# ME433_schematic.net
KiCad netlist of a schematic drawn in EAGLE
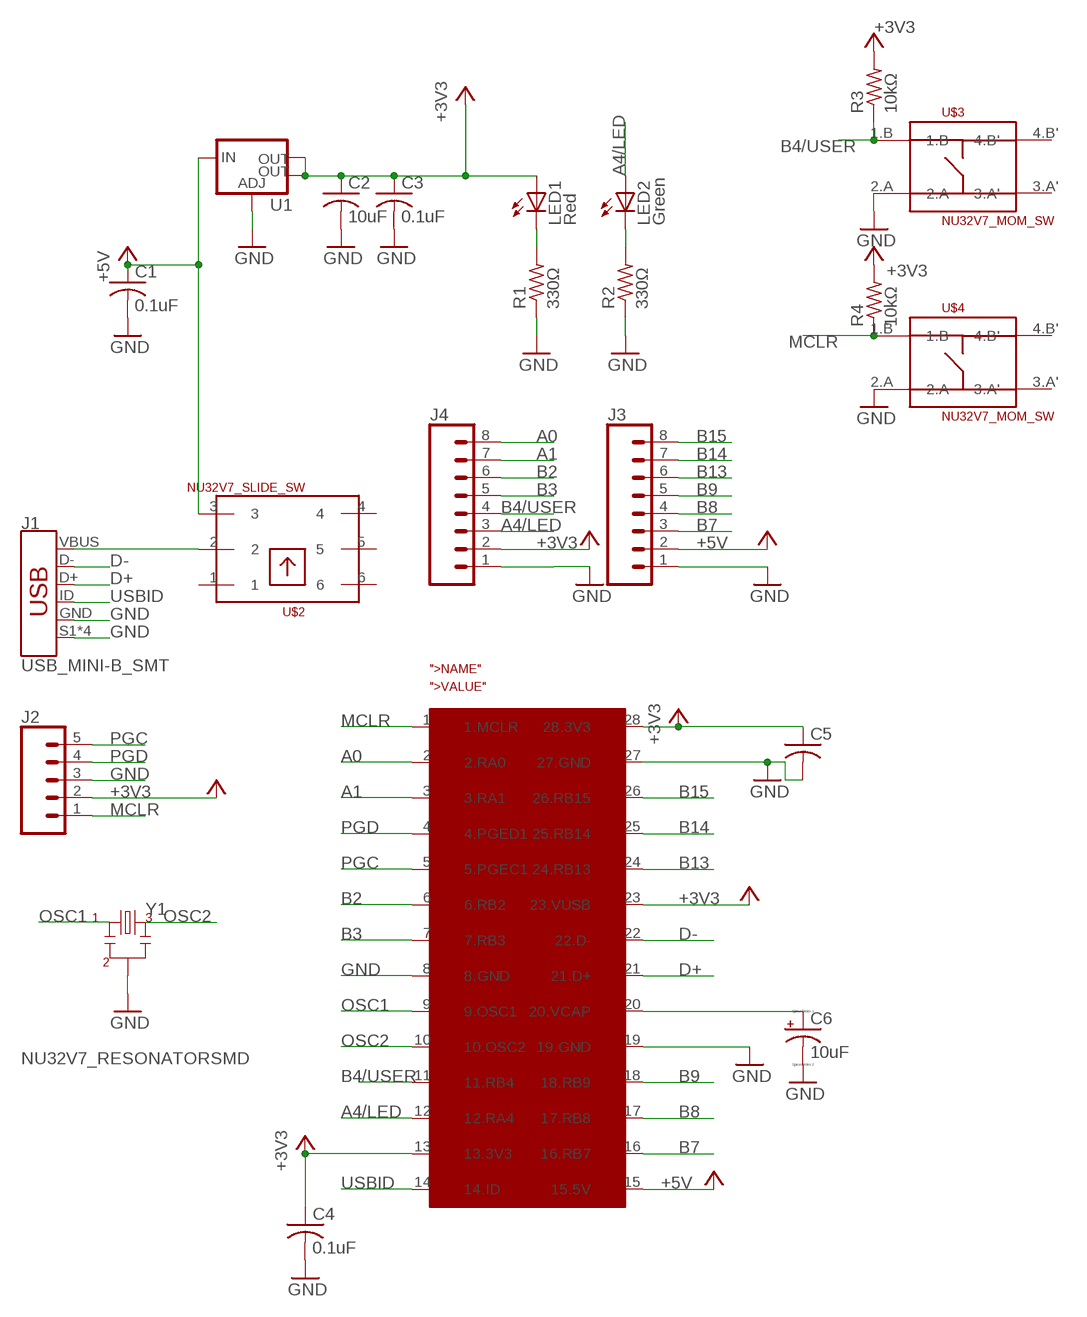
[diagram p0: schematic, sheet 1]

(export (version "E")
  (design (tool "Eeschema 10.0.6"))
  (components
    (comp (ref "C1")
      (value "0.1uF")
      (footprint "eagle-import:C0603")
      (libsource (lib "eagle-import") (part "C-USC0603"))
    )
    (comp (ref "C2")
      (value "10uF")
      (footprint "eagle-import:C0603")
      (libsource (lib "eagle-import") (part "C-USC0603"))
    )
    (comp (ref "C3")
      (value "0.1uF")
      (footprint "eagle-import:C0603")
      (libsource (lib "eagle-import") (part "C-USC0603"))
    )
    (comp (ref "C4")
      (value "0.1uF")
      (footprint "eagle-import:C0603")
      (libsource (lib "eagle-import") (part "C-USC0603"))
    )
    (comp (ref "C5")
      (value "C-USC0603")
      (footprint "eagle-import:C0603")
      (libsource (lib "eagle-import") (part "C-USC0603"))
    )
    (comp (ref "C6")
      (value "10uF")
      (footprint "eagle-import:153CLV-0605")
      (libsource (lib "eagle-import") (part "CPOL-US153CLV-0605"))
    )
    (comp (ref "J1")
      (value "USB_MINI-B_SMT")
      (footprint "eagle-import:USB-MINIB")
      (libsource (lib "eagle-import") (part "USB_MINI-B_SMT"))
    )
    (comp (ref "J2")
      (value "CONN_05")
      (footprint "eagle-import:1X05")
      (libsource (lib "eagle-import") (part "CONN_05"))
    )
    (comp (ref "J3")
      (value "CONN_08\"")
      (footprint "eagle-import:1X08")
      (libsource (lib "eagle-import") (part "CONN_08{dblquote}"))
    )
    (comp (ref "J4")
      (value "CONN_08\"")
      (footprint "eagle-import:1X08")
      (libsource (lib "eagle-import") (part "CONN_08{dblquote}"))
    )
    (comp (ref "LED1")
      (value "Red")
      (footprint "eagle-import:SML0603")
      (libsource (lib "eagle-import") (part "LEDSML0603"))
    )
    (comp (ref "LED2")
      (value "Green")
      (footprint "eagle-import:SML0603")
      (libsource (lib "eagle-import") (part "LEDSML0603"))
    )
    (comp (ref "R1")
      (value "330Ω")
      (footprint "eagle-import:R0603")
      (libsource (lib "eagle-import") (part "R-US_R0603"))
    )
    (comp (ref "R2")
      (value "330Ω")
      (footprint "eagle-import:R0603")
      (libsource (lib "eagle-import") (part "R-US_R0603"))
    )
    (comp (ref "R3")
      (value "10kΩ")
      (footprint "eagle-import:R0603")
      (libsource (lib "eagle-import") (part "R-US_R0603"))
    )
    (comp (ref "R4")
      (value "10kΩ")
      (footprint "eagle-import:R0603")
      (libsource (lib "eagle-import") (part "R-US_R0603"))
    )
    (comp (ref "U$1")
      (value "PIC32")
      (footprint "eagle-import:DIL28-3")
      (libsource (lib "eagle-import") (part "PIC32"))
    )
    (comp (ref "U$2")
      (value "NU32V7_SLIDE_SW")
      (footprint "eagle-import:NU32V7_SLIDE_SW")
      (libsource (lib "eagle-import") (part "NU32V7_SLIDE_SW"))
    )
    (comp (ref "U$3")
      (value "NU32V7_MOM_SW")
      (footprint "eagle-import:NU32V7_MOM_SW")
      (libsource (lib "eagle-import") (part "NU32V7_MOM_SW"))
    )
    (comp (ref "U$4")
      (value "NU32V7_MOM_SW")
      (footprint "eagle-import:NU32V7_MOM_SW")
      (libsource (lib "eagle-import") (part "NU32V7_MOM_SW"))
    )
    (comp (ref "U1")
      (value "NU32V7_V_REG_LM1117SOT223")
      (footprint "eagle-import:NU32V7_SOT223")
      (libsource (lib "eagle-import") (part "NU32V7_V_REG_LM1117SOT223"))
    )
    (comp (ref "Y1")
      (value "NU32V7_RESONATORSMD")
      (footprint "eagle-import:NU32V7_RESONATOR-SMD")
      (libsource (lib "eagle-import") (part "NU32V7_RESONATORSMD"))
    )
  )
  (nets
    (net (code "1") (name "+3V3") (class "Default")
      (node (ref "C2") (pin "1") (pinfunction "1_1") (pintype "passive"))
      (node (ref "C3") (pin "1") (pinfunction "1_1") (pintype "passive"))
      (node (ref "C4") (pin "1") (pinfunction "1_1") (pintype "passive"))
      (node (ref "C5") (pin "1") (pinfunction "1_1") (pintype "passive"))
      (node (ref "J2") (pin "2") (pinfunction "2_2") (pintype "passive"))
      (node (ref "J4") (pin "2") (pinfunction "2_2") (pintype "passive"))
      (node (ref "LED1") (pin "A") (pinfunction "A_A") (pintype "passive"))
      (node (ref "R3") (pin "2") (pinfunction "2_2") (pintype "passive"))
      (node (ref "R4") (pin "2") (pinfunction "2_2") (pintype "passive"))
      (node (ref "U$1") (pin "13") (pinfunction "13.3V3_13") (pintype "bidirectional"))
      (node (ref "U$1") (pin "23") (pinfunction "23.VUSB_23") (pintype "bidirectional"))
      (node (ref "U$1") (pin "28") (pinfunction "28.3V3_28") (pintype "bidirectional"))
      (node (ref "U1") (pin "2") (pinfunction "OUT_2") (pintype "output"))
      (node (ref "U1") (pin "4") (pinfunction "OUT_4") (pintype "output"))
    )
    (net (code "2") (name "+5V") (class "Default")
      (node (ref "C1") (pin "1") (pinfunction "1_1") (pintype "passive"))
      (node (ref "J3") (pin "2") (pinfunction "2_2") (pintype "passive"))
      (node (ref "U$1") (pin "15") (pinfunction "15.5V_15") (pintype "bidirectional"))
      (node (ref "U$2") (pin "3") (pinfunction "3_3") (pintype "bidirectional"))
      (node (ref "U1") (pin "3") (pinfunction "IN_3") (pintype "input"))
    )
    (net (code "3") (name "/A0") (class "Default")
      (node (ref "J4") (pin "8") (pinfunction "8_8") (pintype "passive"))
      (node (ref "U$1") (pin "2") (pinfunction "2.RA0_2") (pintype "bidirectional"))
    )
    (net (code "4") (name "/A1") (class "Default")
      (node (ref "J4") (pin "7") (pinfunction "7_7") (pintype "passive"))
      (node (ref "U$1") (pin "3") (pinfunction "3.RA1_3") (pintype "bidirectional"))
    )
    (net (code "5") (name "/A4{slash}LED") (class "Default")
      (node (ref "J4") (pin "3") (pinfunction "3_3") (pintype "passive"))
      (node (ref "LED2") (pin "A") (pinfunction "A_A") (pintype "passive"))
      (node (ref "U$1") (pin "12") (pinfunction "12.RA4_12") (pintype "bidirectional"))
    )
    (net (code "6") (name "/B2") (class "Default")
      (node (ref "J4") (pin "6") (pinfunction "6_6") (pintype "passive"))
      (node (ref "U$1") (pin "6") (pinfunction "6.RB2_6") (pintype "bidirectional"))
    )
    (net (code "7") (name "/B3") (class "Default")
      (node (ref "J4") (pin "5") (pinfunction "5_5") (pintype "passive"))
      (node (ref "U$1") (pin "7") (pinfunction "7.RB3_7") (pintype "bidirectional"))
    )
    (net (code "8") (name "/B4{slash}USER") (class "Default")
      (node (ref "J4") (pin "4") (pinfunction "4_4") (pintype "passive"))
      (node (ref "R3") (pin "1") (pinfunction "1_1") (pintype "passive"))
      (node (ref "U$1") (pin "11") (pinfunction "11.RB4_11") (pintype "bidirectional"))
      (node (ref "U$3") (pin "1.B") (pinfunction "1.B_1.B") (pintype "bidirectional"))
    )
    (net (code "9") (name "/B7") (class "Default")
      (node (ref "J3") (pin "3") (pinfunction "3_3") (pintype "passive"))
      (node (ref "U$1") (pin "16") (pinfunction "16.RB7_16") (pintype "bidirectional"))
    )
    (net (code "10") (name "/B8") (class "Default")
      (node (ref "J3") (pin "4") (pinfunction "4_4") (pintype "passive"))
      (node (ref "U$1") (pin "17") (pinfunction "17.RB8_17") (pintype "bidirectional"))
    )
    (net (code "11") (name "/B9") (class "Default")
      (node (ref "J3") (pin "5") (pinfunction "5_5") (pintype "passive"))
      (node (ref "U$1") (pin "18") (pinfunction "18.RB9_18") (pintype "bidirectional"))
    )
    (net (code "12") (name "/B13") (class "Default")
      (node (ref "J3") (pin "6") (pinfunction "6_6") (pintype "passive"))
      (node (ref "U$1") (pin "24") (pinfunction "24.RB13_24") (pintype "bidirectional"))
    )
    (net (code "13") (name "/B14") (class "Default")
      (node (ref "J3") (pin "7") (pinfunction "7_7") (pintype "passive"))
      (node (ref "U$1") (pin "25") (pinfunction "25.RB14_25") (pintype "bidirectional"))
    )
    (net (code "14") (name "/B15") (class "Default")
      (node (ref "J3") (pin "8") (pinfunction "8_8") (pintype "passive"))
      (node (ref "U$1") (pin "26") (pinfunction "26.RB15_26") (pintype "bidirectional"))
    )
    (net (code "15") (name "/D+") (class "Default")
      (node (ref "J1") (pin "D+") (pinfunction "D+_D+") (pintype "bidirectional"))
      (node (ref "U$1") (pin "21") (pinfunction "21.D+_21") (pintype "bidirectional"))
    )
    (net (code "16") (name "/D-") (class "Default")
      (node (ref "J1") (pin "D-") (pinfunction "D-_D-") (pintype "bidirectional"))
      (node (ref "U$1") (pin "22") (pinfunction "22.D-_22") (pintype "bidirectional"))
    )
    (net (code "17") (name "/MCLR") (class "Default")
      (node (ref "J2") (pin "1") (pinfunction "1_1") (pintype "passive"))
      (node (ref "R4") (pin "1") (pinfunction "1_1") (pintype "passive"))
      (node (ref "U$1") (pin "1") (pinfunction "1.MCLR_1") (pintype "bidirectional"))
      (node (ref "U$4") (pin "1.B") (pinfunction "1.B_1.B") (pintype "bidirectional"))
    )
    (net (code "18") (name "/OSC1") (class "Default")
      (node (ref "U$1") (pin "9") (pinfunction "9.OSC1_9") (pintype "bidirectional"))
      (node (ref "Y1") (pin "1") (pinfunction "1_1") (pintype "passive"))
    )
    (net (code "19") (name "/OSC2") (class "Default")
      (node (ref "U$1") (pin "10") (pinfunction "10.OSC2_10") (pintype "bidirectional"))
      (node (ref "Y1") (pin "3") (pinfunction "3_3") (pintype "passive"))
    )
    (net (code "20") (name "/PGC") (class "Default")
      (node (ref "J2") (pin "5") (pinfunction "5_5") (pintype "passive"))
      (node (ref "U$1") (pin "5") (pinfunction "5.PGEC1_5") (pintype "bidirectional"))
    )
    (net (code "21") (name "/PGD") (class "Default")
      (node (ref "J2") (pin "4") (pinfunction "4_4") (pintype "passive"))
      (node (ref "U$1") (pin "4") (pinfunction "4.PGED1_4") (pintype "bidirectional"))
    )
    (net (code "22") (name "/USBID") (class "Default")
      (node (ref "J1") (pin "ID") (pinfunction "ID_ID") (pintype "bidirectional"))
      (node (ref "U$1") (pin "14") (pinfunction "14.ID_14") (pintype "bidirectional"))
    )
    (net (code "23") (name "GND") (class "Default")
      (node (ref "C1") (pin "2") (pinfunction "2_2") (pintype "passive"))
      (node (ref "C2") (pin "2") (pinfunction "2_2") (pintype "passive"))
      (node (ref "C3") (pin "2") (pinfunction "2_2") (pintype "passive"))
      (node (ref "C4") (pin "2") (pinfunction "2_2") (pintype "passive"))
      (node (ref "C5") (pin "2") (pinfunction "2_2") (pintype "passive"))
      (node (ref "C6") (pin "-") (pinfunction "-_-") (pintype "passive"))
      (node (ref "J1") (pin "GND") (pinfunction "GND_GND") (pintype "power_in"))
      (node (ref "J1") (pin "S1") (pinfunction "SHIELD_S1") (pintype "bidirectional"))
      (node (ref "J1") (pin "S2") (pinfunction "SHIELD_S2") (pintype "bidirectional"))
      (node (ref "J1") (pin "S3") (pinfunction "SHIELD_S3") (pintype "bidirectional"))
      (node (ref "J1") (pin "S4") (pinfunction "SHIELD_S4") (pintype "bidirectional"))
      (node (ref "J2") (pin "3") (pinfunction "3_3") (pintype "passive"))
      (node (ref "J3") (pin "1") (pinfunction "1_1") (pintype "passive"))
      (node (ref "J4") (pin "1") (pinfunction "1_1") (pintype "passive"))
      (node (ref "R1") (pin "1") (pinfunction "1_1") (pintype "passive"))
      (node (ref "R2") (pin "1") (pinfunction "1_1") (pintype "passive"))
      (node (ref "U$1") (pin "19") (pinfunction "19.GND_19") (pintype "bidirectional"))
      (node (ref "U$1") (pin "27") (pinfunction "27.GND_27") (pintype "bidirectional"))
      (node (ref "U$1") (pin "8") (pinfunction "8.GND_8") (pintype "bidirectional"))
      (node (ref "U$3") (pin "2.A") (pinfunction "2.A_2.A") (pintype "bidirectional"))
      (node (ref "U$4") (pin "2.A") (pinfunction "2.A_2.A") (pintype "bidirectional"))
      (node (ref "U1") (pin "1") (pinfunction "ADJ_1") (pintype "input"))
      (node (ref "Y1") (pin "2") (pinfunction "2_2") (pintype "passive"))
    )
    (net (code "24") (name "Net-(J1-PadVBUS)") (class "Default")
      (node (ref "J1") (pin "VBUS") (pinfunction "VBUS_VBUS") (pintype "power_in"))
      (node (ref "U$2") (pin "2") (pinfunction "2_2") (pintype "bidirectional"))
    )
    (net (code "25") (name "Net-(LED1-PadC)") (class "Default")
      (node (ref "LED1") (pin "C") (pinfunction "C_C") (pintype "passive"))
      (node (ref "R1") (pin "2") (pinfunction "2_2") (pintype "passive"))
    )
    (net (code "26") (name "Net-(LED2-PadC)") (class "Default")
      (node (ref "LED2") (pin "C") (pinfunction "C_C") (pintype "passive"))
      (node (ref "R2") (pin "2") (pinfunction "2_2") (pintype "passive"))
    )
    (net (code "27") (name "Net-(U$1-20.VCAP)") (class "Default")
      (node (ref "C6") (pin "+") (pinfunction "+_+") (pintype "passive"))
      (node (ref "U$1") (pin "20") (pinfunction "20.VCAP_20") (pintype "bidirectional"))
    )
    (net (code "28") (name "unconnected-(U$2-Pad1)") (class "Default")
      (node (ref "U$2") (pin "1") (pinfunction "1_1") (pintype "bidirectional"))
    )
    (net (code "29") (name "unconnected-(U$2-Pad4)") (class "Default")
      (node (ref "U$2") (pin "4") (pinfunction "4_4") (pintype "bidirectional"))
    )
    (net (code "30") (name "unconnected-(U$2-Pad5)") (class "Default")
      (node (ref "U$2") (pin "5") (pinfunction "5_5") (pintype "bidirectional"))
    )
    (net (code "31") (name "unconnected-(U$2-Pad6)") (class "Default")
      (node (ref "U$2") (pin "6") (pinfunction "6_6") (pintype "bidirectional"))
    )
    (net (code "32") (name "unconnected-(U$3-Pad3.A')") (class "Default")
      (node (ref "U$3") (pin "3.A'") (pinfunction "3.A'_3.A'") (pintype "bidirectional"))
    )
    (net (code "33") (name "unconnected-(U$3-Pad4.B')") (class "Default")
      (node (ref "U$3") (pin "4.B'") (pinfunction "4.B'_4.B'") (pintype "bidirectional"))
    )
    (net (code "34") (name "unconnected-(U$4-Pad3.A')") (class "Default")
      (node (ref "U$4") (pin "3.A'") (pinfunction "3.A'_3.A'") (pintype "bidirectional"))
    )
    (net (code "35") (name "unconnected-(U$4-Pad4.B')") (class "Default")
      (node (ref "U$4") (pin "4.B'") (pinfunction "4.B'_4.B'") (pintype "bidirectional"))
    )
  )
)
